# CAN_Interface.net
KiCad netlist of a schematic drawn in Altium Designer
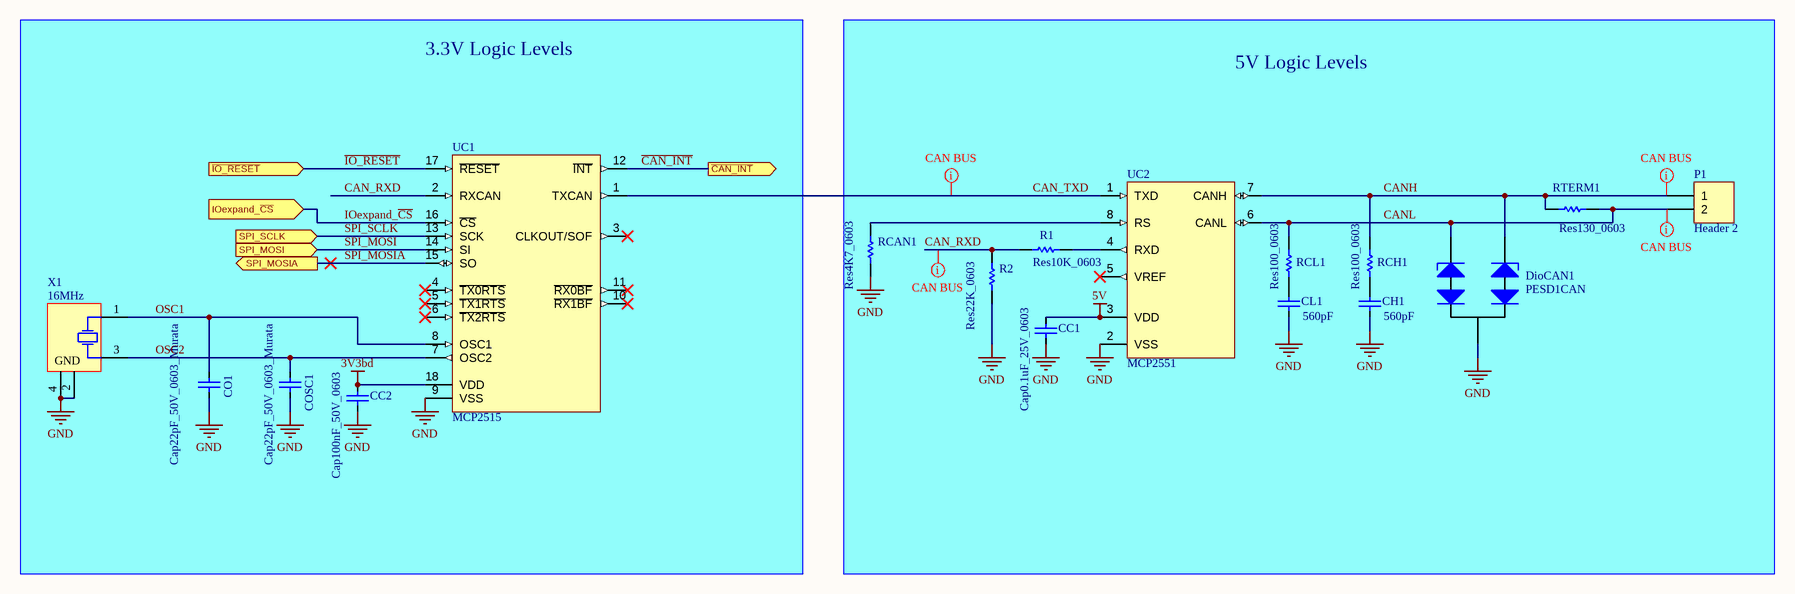
[diagram p0: CAN_Interface.SchDoc]

(export (version "E")
  (design (tool "Eeschema 10.0.6"))
  (components
    (comp (ref "CC1")
      (value "Cap0.1uF_25V_0603")
      (footprint "0603C_L")
      (libsource (lib " Advanced] Training Course - A365") (part "CAP General"))
    )
    (comp (ref "CC2")
      (value "Cap100nF_50V_0603")
      (footprint "0603C_L")
      (libsource (lib " Advanced] Training Course - A365") (part "CAP General"))
    )
    (comp (ref "CH1")
      (value "560pF")
      (footprint "0603C_L")
      (description "560pF 25V 0603")
      (fields (field (name "Comment") "CAP General"))
      (libsource (lib " Advanced] Training Course - A365") (part "CAP General"))
    )
    (comp (ref "CL1")
      (value "560pF")
      (footprint "0603C_L")
      (description "560pF 25V 0603")
      (fields (field (name "Comment") "CAP General"))
      (libsource (lib " Advanced] Training Course - A365") (part "CAP General"))
    )
    (comp (ref "CO1")
      (value "Cap22pF_50V_0603_Murata")
      (footprint "0603C_L")
      (fields (field (name "TOLERANCE") "5%"))
      (libsource (lib " Advanced] Training Course - A365") (part "CAP General"))
    )
    (comp (ref "COSC1")
      (value "Cap22pF_50V_0603_Murata")
      (footprint "0603C_L")
      (fields (field (name "TOLERANCE") "5%"))
      (libsource (lib " Advanced] Training Course - A365") (part "CAP General"))
    )
    (comp (ref "DioCAN1")
      (value "PESD1CAN")
      (footprint "SOT323")
      (description "Trans Voltage Suppressor Diode, 150W, 24V V(RWM), Bidirectional, 2 Element, Silicon")
      (fields (field (name "MANUFACTURER") "Nexperia USA Inc."))
      (libsource (lib " Advanced] Training Course - A365") (part "PESD1CAN"))
    )
    (comp (ref "P1")
      (value "Header 2")
      (footprint "HDR1X2")
      (description "Header, 2-Pin")
      (fields (field (name "PUBLISHER") "Altium Limited"))
      (libsource (lib " Advanced] Training Course - A365") (part "Header 2"))
    )
    (comp (ref "R1")
      (value "Res10K_0603")
      (footprint "0603_L")
      (fields
        (field (name "MANUFACTURER") "Panasonic Electronic Components")
        (field (name "MANUFACTURER PART NUMBER") "ERJ-3GEYJ102V")
        (field (name "TOLERANCE") "5%")
      )
      (libsource (lib " Advanced] Training Course - A365") (part "Resistor General"))
    )
    (comp (ref "R2")
      (value "Res22K_0603")
      (footprint "0603_L")
      (description "RES22K 0.5% 0603")
      (fields
        (field (name "MANUFACTURER") "Yageo")
        (field (name "MANUFACTURER PART NUMBER") "RT0603DRD0722KL")
      )
      (libsource (lib " Advanced] Training Course - A365") (part "Resistor General"))
    )
    (comp (ref "RCAN1")
      (value "Res4K7_0603")
      (footprint "0603_L")
      (fields (field (name "MANUFACTURER") "Yageo") (field (name "TOLERANCE") "0.5%"))
      (libsource (lib " Advanced] Training Course - A365") (part "Resistor General"))
    )
    (comp (ref "RCH1")
      (value "Res100_0603")
      (footprint "0603_L")
      (fields (field (name "MANUFACTURER") "Panasonic Electronic Components") (field (name "TOLERANCE") "5%"))
      (libsource (lib " Advanced] Training Course - A365") (part "Resistor General"))
    )
    (comp (ref "RCL1")
      (value "Res100_0603")
      (footprint "0603_L")
      (fields (field (name "MANUFACTURER") "Panasonic Electronic Components") (field (name "TOLERANCE") "5%"))
      (libsource (lib " Advanced] Training Course - A365") (part "Resistor General"))
    )
    (comp (ref "RTERM1")
      (value "Res130_0603")
      (footprint "0603_L")
      (fields (field (name "MANUFACTURER") "Panasonic Electronic Components") (field (name "TOLERANCE") "5%"))
      (libsource (lib " Advanced] Training Course - A365") (part "Resistor General"))
    )
    (comp (ref "UC1")
      (value "MCP2515")
      (footprint "SOIC-SO18_M")
      (description "Stand-Alone CAN Controller With SPI Interface, 18-Pin SOIC, Extended Temperature")
      (fields
        (field (name "MANUFACTURER") "Microchip")
        (field (name "MANUFACTURER PART NUMBER") "MCP2515-E/SO")
        (field (name "AVAILABLE PREVIEW IMAGES") "2D")
      )
      (libsource (lib " Advanced] Training Course - A365") (part "MCP2515"))
    )
    (comp (ref "UC2")
      (value "MCP2551")
      (footprint "SOIC-SN8_N")
      (description "High-Speed CAN Transceiver, 8-Pin SOIC, Extended Temperature")
      (fields
        (field (name "MANUFACTURER") "Microchip")
        (field (name "MANUFACTURER PART NUMBER") "MCP2551-E/SN")
        (field (name "AVAILABLE PREVIEW IMAGES") "2D")
      )
      (libsource (lib " Advanced] Training Course - A365") (part "MCP2551"))
    )
    (comp (ref "X1")
      (value "Crystal 4Pin")
      (footprint "FP-ABM8-MFG")
      (description "Crystal 16MHz ±20ppm 18pF SMD-4 3.2mm x 2.5mm CSTCE16M0V53-R0 ABM8-16.000MHZ-B2-T")
      (fields (field (name "TOLERANCE") "20ppm") (field (name "FREQUENCY") "16MHz"))
      (libsource (lib " Advanced] Training Course - A365") (part "Crystal 4Pin"))
    )
  )
  (nets
    (net (code "1") (name "/CANH") (class "Default")
      (node (ref "DioCAN1") (pin "1") (pinfunction "A_1") (pintype "passive"))
      (node (ref "P1") (pin "1") (pinfunction "1_1") (pintype "passive"))
      (node (ref "RCH1") (pin "2") (pinfunction "2_2") (pintype "passive"))
      (node (ref "RTERM1") (pin "2") (pinfunction "2_2") (pintype "passive"))
      (node (ref "UC2") (pin "7") (pinfunction "CANH_7") (pintype "bidirectional"))
    )
    (net (code "2") (name "/CANL") (class "Default")
      (node (ref "DioCAN1") (pin "2") (pinfunction "K_2") (pintype "passive"))
      (node (ref "P1") (pin "2") (pinfunction "2_2") (pintype "passive"))
      (node (ref "RCL1") (pin "2") (pinfunction "2_2") (pintype "passive"))
      (node (ref "RTERM1") (pin "1") (pinfunction "1_1") (pintype "passive"))
      (node (ref "UC2") (pin "6") (pinfunction "CANL_6") (pintype "bidirectional"))
    )
    (net (code "3") (name "/CAN_INT") (class "Default")
      (node (ref "UC1") (pin "12") (pinfunction "~{INT}_12") (pintype "output"))
    )
    (net (code "4") (name "/CAN_RXD") (class "Default")
      (node (ref "R1") (pin "2") (pinfunction "2_2") (pintype "passive"))
      (node (ref "R2") (pin "2") (pinfunction "2_2") (pintype "passive"))
      (node (ref "UC1") (pin "2") (pinfunction "RXCAN_2") (pintype "input"))
    )
    (net (code "5") (name "/CAN_TXD") (class "Default")
      (node (ref "UC1") (pin "1") (pinfunction "TXCAN_1") (pintype "output"))
      (node (ref "UC2") (pin "1") (pinfunction "TXD_1") (pintype "input"))
    )
    (net (code "6") (name "/IO_RESET") (class "Default")
      (node (ref "UC1") (pin "17") (pinfunction "~{RESET}_17") (pintype "input"))
    )
    (net (code "7") (name "/IOexpand_~{CS}") (class "Default")
      (node (ref "UC1") (pin "16") (pinfunction "~{CS}_16") (pintype "input"))
    )
    (net (code "8") (name "/OSC1") (class "Default")
      (node (ref "CO1") (pin "2") (pinfunction "2_2") (pintype "passive"))
      (node (ref "UC1") (pin "8") (pinfunction "OSC1_8") (pintype "input"))
      (node (ref "X1") (pin "1") (pinfunction "1_1") (pintype "passive"))
    )
    (net (code "9") (name "/OSC2") (class "Default")
      (node (ref "COSC1") (pin "2") (pinfunction "2_2") (pintype "passive"))
      (node (ref "UC1") (pin "7") (pinfunction "OSC2_7") (pintype "output"))
      (node (ref "X1") (pin "3") (pinfunction "3_3") (pintype "passive"))
    )
    (net (code "10") (name "/SPI_MOSI") (class "Default")
      (node (ref "UC1") (pin "14") (pinfunction "SI_14") (pintype "input"))
    )
    (net (code "11") (name "/SPI_MOSIA") (class "Default")
      (node (ref "UC1") (pin "15") (pinfunction "SO_15") (pintype "bidirectional"))
    )
    (net (code "12") (name "/SPI_SCLK") (class "Default")
      (node (ref "UC1") (pin "13") (pinfunction "SCK_13") (pintype "input"))
    )
    (net (code "13") (name "3V3bd") (class "Default")
      (node (ref "CC2") (pin "2") (pinfunction "2_2") (pintype "passive"))
      (node (ref "UC1") (pin "18") (pinfunction "VDD_18") (pintype "power_in"))
    )
    (net (code "14") (name "5V") (class "Default")
      (node (ref "CC1") (pin "2") (pinfunction "2_2") (pintype "passive"))
      (node (ref "UC2") (pin "3") (pinfunction "VDD_3") (pintype "power_in"))
    )
    (net (code "15") (name "GND") (class "Default")
      (node (ref "CC1") (pin "1") (pinfunction "1_1") (pintype "passive"))
      (node (ref "CC2") (pin "1") (pinfunction "1_1") (pintype "passive"))
      (node (ref "CH1") (pin "2") (pinfunction "2_2") (pintype "passive"))
      (node (ref "CL1") (pin "1") (pinfunction "1_1") (pintype "passive"))
      (node (ref "CO1") (pin "1") (pinfunction "1_1") (pintype "passive"))
      (node (ref "COSC1") (pin "1") (pinfunction "1_1") (pintype "passive"))
      (node (ref "DioCAN1") (pin "3") (pinfunction "3_3") (pintype "passive"))
      (node (ref "R2") (pin "1") (pinfunction "1_1") (pintype "passive"))
      (node (ref "RCAN1") (pin "1") (pinfunction "1_1") (pintype "passive"))
      (node (ref "UC1") (pin "9") (pinfunction "VSS_9") (pintype "power_in"))
      (node (ref "UC2") (pin "2") (pinfunction "VSS_2") (pintype "power_in"))
      (node (ref "X1") (pin "2") (pinfunction "GND_2") (pintype "power_in"))
      (node (ref "X1") (pin "4") (pinfunction "GND_4") (pintype "power_in"))
    )
    (net (code "16") (name "Net-(CH1-Pad1)") (class "Default")
      (node (ref "CH1") (pin "1") (pinfunction "1_1") (pintype "passive"))
      (node (ref "RCH1") (pin "1") (pinfunction "1_1") (pintype "passive"))
    )
    (net (code "17") (name "Net-(CL1-Pad2)") (class "Default")
      (node (ref "CL1") (pin "2") (pinfunction "2_2") (pintype "passive"))
      (node (ref "RCL1") (pin "1") (pinfunction "1_1") (pintype "passive"))
    )
    (net (code "18") (name "Net-(UC2-RS)") (class "Default")
      (node (ref "RCAN1") (pin "2") (pinfunction "2_2") (pintype "passive"))
      (node (ref "UC2") (pin "8") (pinfunction "RS_8") (pintype "input"))
    )
    (net (code "19") (name "Net-(UC2-RXD)") (class "Default")
      (node (ref "R1") (pin "1") (pinfunction "1_1") (pintype "passive"))
      (node (ref "UC2") (pin "4") (pinfunction "RXD_4") (pintype "output"))
    )
    (net (code "20") (name "unconnected-(UC1-CLKOUT{slash}SOF-Pad3)") (class "Default")
      (node (ref "UC1") (pin "3") (pinfunction "CLKOUT/SOF_3") (pintype "output+no_connect"))
    )
    (net (code "21") (name "unconnected-(UC1-~{RX0BF}-Pad11)") (class "Default")
      (node (ref "UC1") (pin "11") (pinfunction "~{RX0BF}_11") (pintype "output+no_connect"))
    )
    (net (code "22") (name "unconnected-(UC1-~{RX1BF}-Pad10)") (class "Default")
      (node (ref "UC1") (pin "10") (pinfunction "~{RX1BF}_10") (pintype "output+no_connect"))
    )
    (net (code "23") (name "unconnected-(UC1-~{TX0RTS}-Pad4)") (class "Default")
      (node (ref "UC1") (pin "4") (pinfunction "~{TX0RTS}_4") (pintype "input+no_connect"))
    )
    (net (code "24") (name "unconnected-(UC1-~{TX1RTS}-Pad5)") (class "Default")
      (node (ref "UC1") (pin "5") (pinfunction "~{TX1RTS}_5") (pintype "input+no_connect"))
    )
    (net (code "25") (name "unconnected-(UC1-~{TX2RTS}-Pad6)") (class "Default")
      (node (ref "UC1") (pin "6") (pinfunction "~{TX2RTS}_6") (pintype "input+no_connect"))
    )
    (net (code "26") (name "unconnected-(UC2-VREF-Pad5)") (class "Default")
      (node (ref "UC2") (pin "5") (pinfunction "VREF_5") (pintype "output+no_connect"))
    )
  )
)
